# SCH_NFC__2021-12-08.net
KiCad netlist of a schematic drawn in EasyEDA
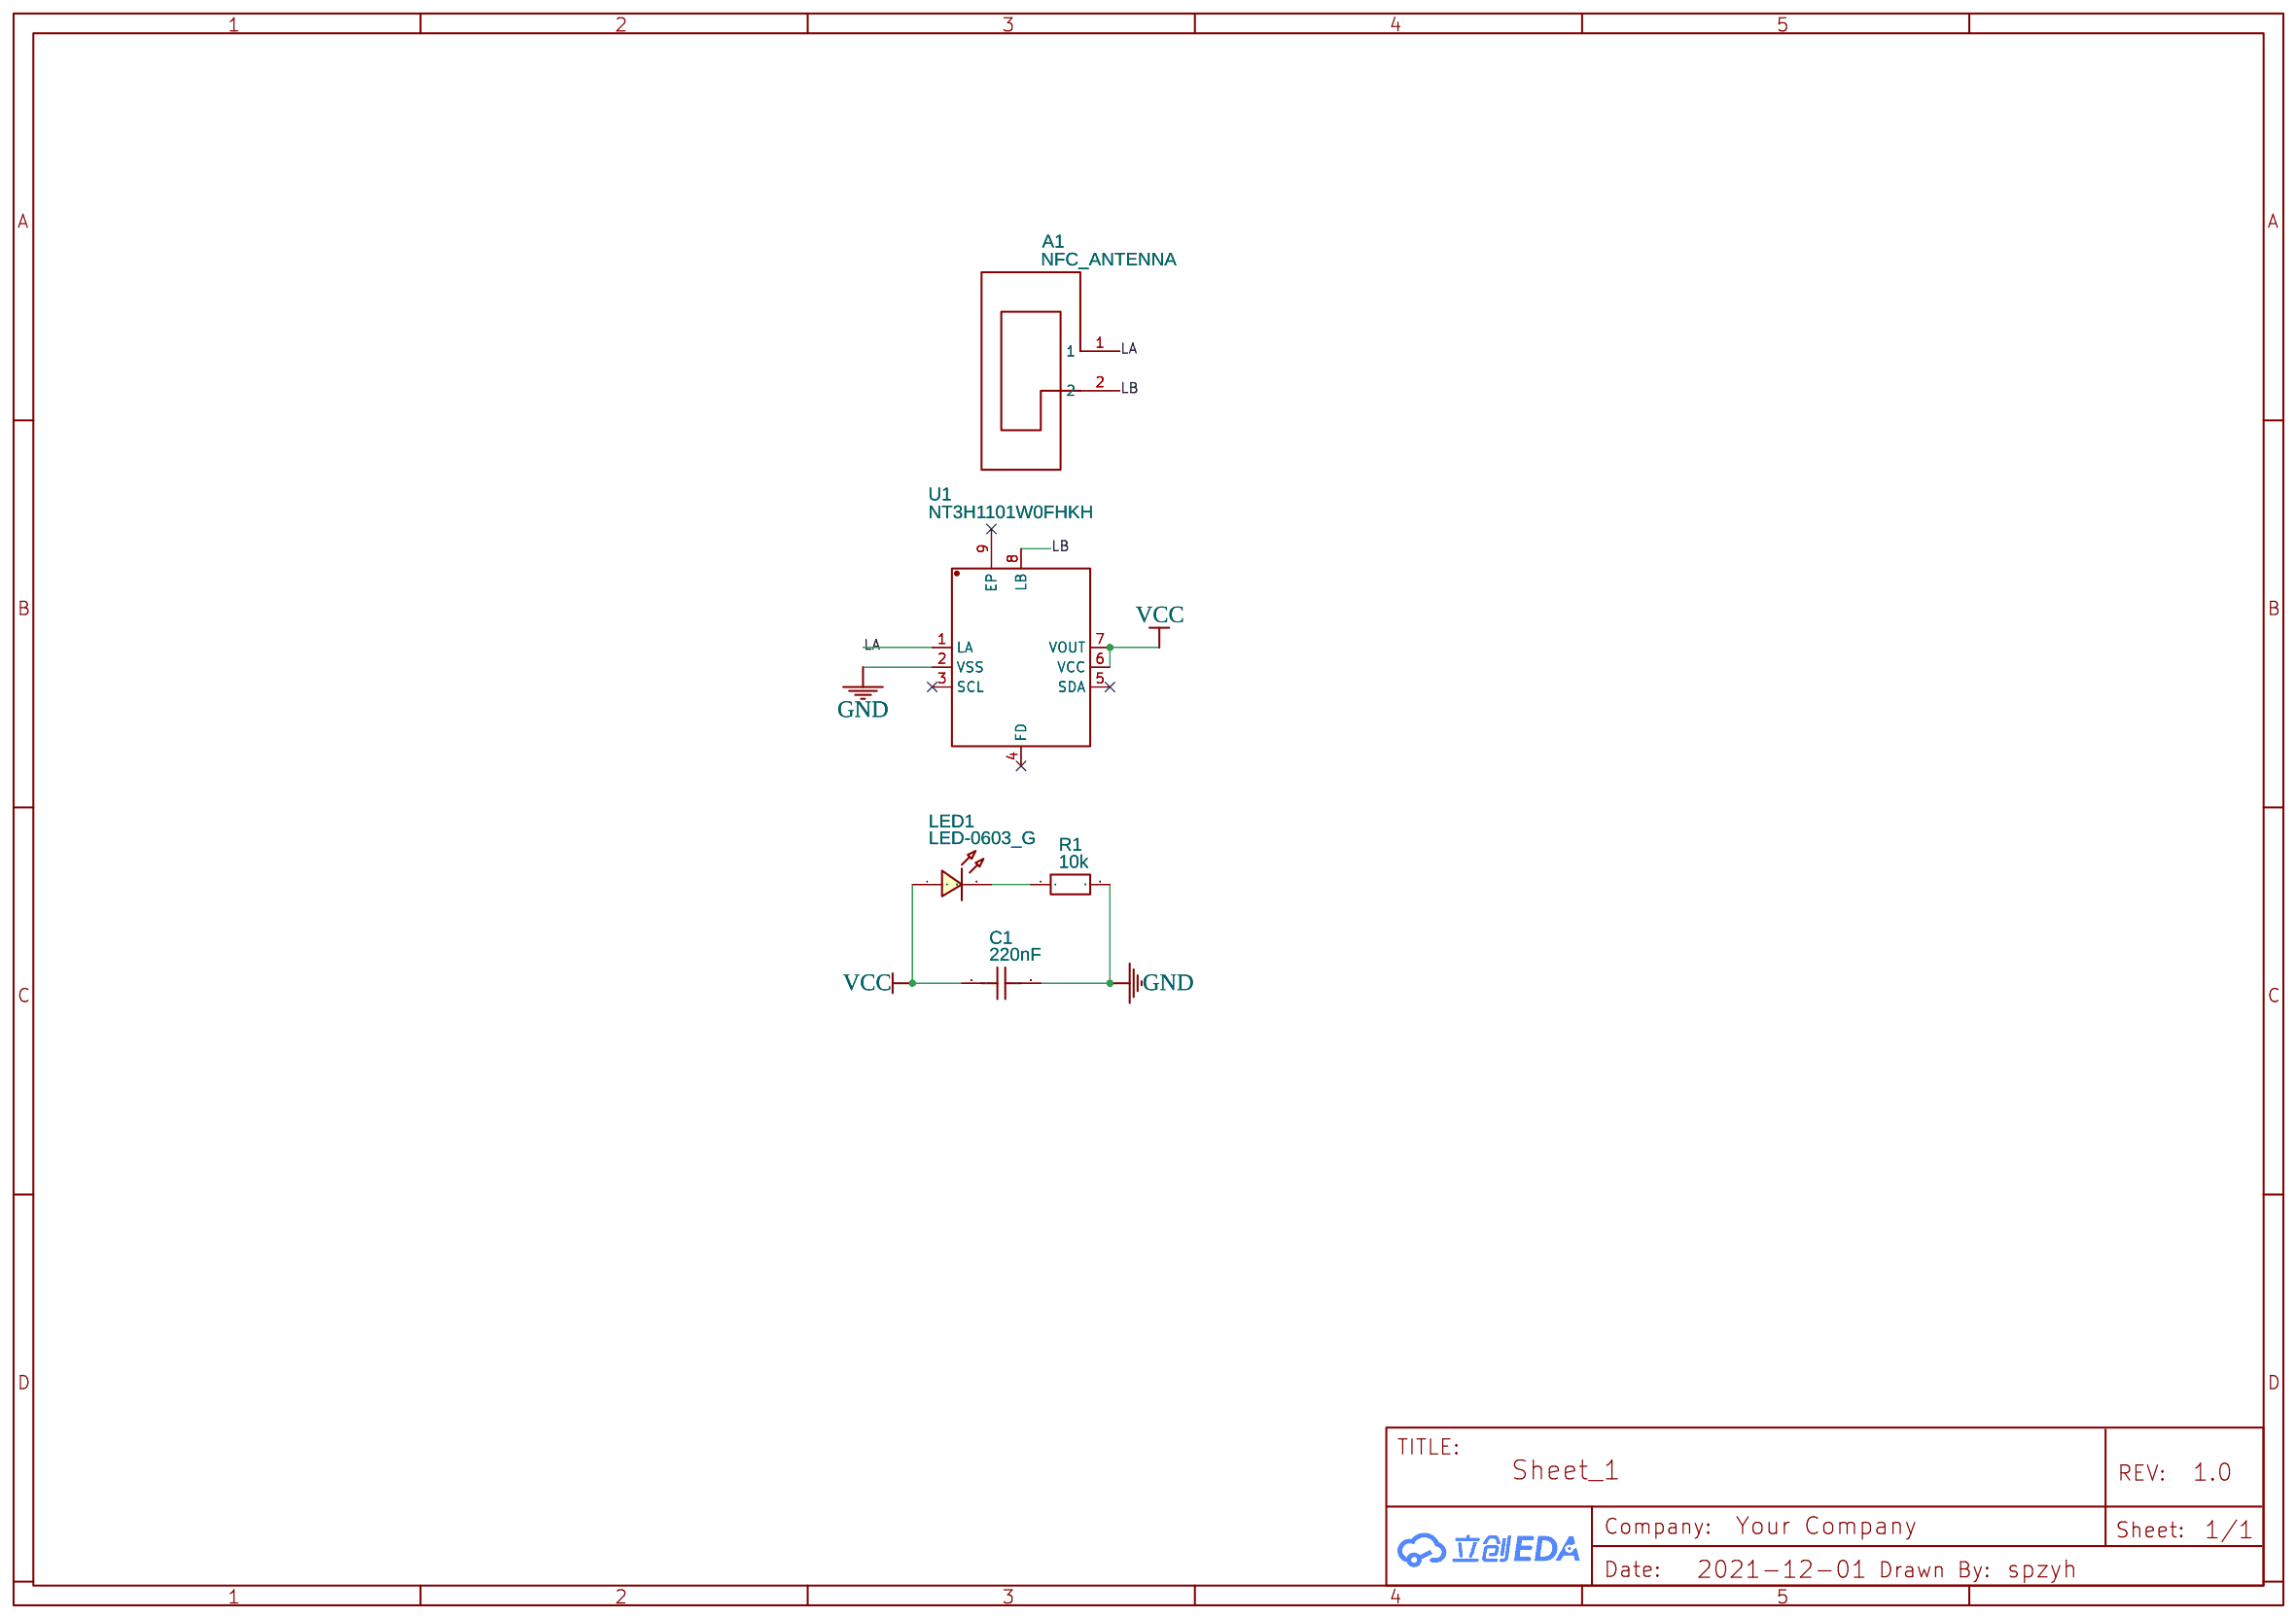
[diagram p0: schematic sheet]

(export (version "E")
  (design (tool "Eeschema 10.0.6"))
  (components
    (comp (ref "A1") (value "NFC_ANTENNA") (libsource (lib "") (part "NFC_ANTENNA")))
    (comp (ref "C1") (value "220nF") (libsource (lib "") (part "C_0603_US")))
    (comp (ref "LED1")
      (value "LED-0603_G")
      (fields
        (field (name "BOM_Manufacturer Part") "19-217/GHC-YR1S2/3T")
        (field (name "BOM_Supplier Part") "C72043")
      )
      (libsource (lib "") (part "LED-0603_G"))
    )
    (comp (ref "R1") (value "10k") (libsource (lib "") (part "R_0603_EU")))
    (comp (ref "U1")
      (value "NT3H1101W0FHKH")
      (fields (field (name "BOM_Supplier Part") "C73156"))
      (libsource (lib "") (part "NT3H1101W0FHKH"))
    )
  )
  (nets
    (net (code "1") (name "/LA") (class "Default")
      (node (ref "A1") (pin "1") (pinfunction "1_1") (pintype "unspecified"))
      (node (ref "U1") (pin "1") (pinfunction "LA_1") (pintype "unspecified"))
    )
    (net (code "2") (name "/LB") (class "Default")
      (node (ref "A1") (pin "2") (pinfunction "2_2") (pintype "unspecified"))
      (node (ref "U1") (pin "8") (pinfunction "LB_8") (pintype "unspecified"))
    )
    (net (code "3") (name "GND") (class "Default")
      (node (ref "C1") (pin "2") (pinfunction "2_2") (pintype "unspecified"))
      (node (ref "R1") (pin "2") (pinfunction "2_2") (pintype "unspecified"))
      (node (ref "U1") (pin "2") (pinfunction "VSS_2") (pintype "unspecified"))
    )
    (net (code "4") (name "Net-(LED1-Pad2)") (class "Default")
      (node (ref "LED1") (pin "2") (pinfunction "2_2") (pintype "unspecified"))
      (node (ref "R1") (pin "1") (pinfunction "1_1") (pintype "unspecified"))
    )
    (net (code "5") (name "VCC") (class "Default")
      (node (ref "C1") (pin "1") (pinfunction "1_1") (pintype "unspecified"))
      (node (ref "LED1") (pin "1") (pinfunction "1_1") (pintype "unspecified"))
      (node (ref "U1") (pin "6") (pinfunction "VCC_6") (pintype "unspecified"))
      (node (ref "U1") (pin "7") (pinfunction "VOUT_7") (pintype "unspecified"))
    )
    (net (code "6") (name "unconnected-(U1-EP-Pad9)") (class "Default")
      (node (ref "U1") (pin "9") (pinfunction "EP_9") (pintype "unspecified+no_connect"))
    )
    (net (code "7") (name "unconnected-(U1-FD-Pad4)") (class "Default")
      (node (ref "U1") (pin "4") (pinfunction "FD_4") (pintype "unspecified+no_connect"))
    )
    (net (code "8") (name "unconnected-(U1-SCL-Pad3)") (class "Default")
      (node (ref "U1") (pin "3") (pinfunction "SCL_3") (pintype "unspecified+no_connect"))
    )
    (net (code "9") (name "unconnected-(U1-SDA-Pad5)") (class "Default")
      (node (ref "U1") (pin "5") (pinfunction "SDA_5") (pintype "unspecified+no_connect"))
    )
  )
)
